# GFB_MCU_Testboard.net
KiCad netlist of a schematic drawn in EAGLE
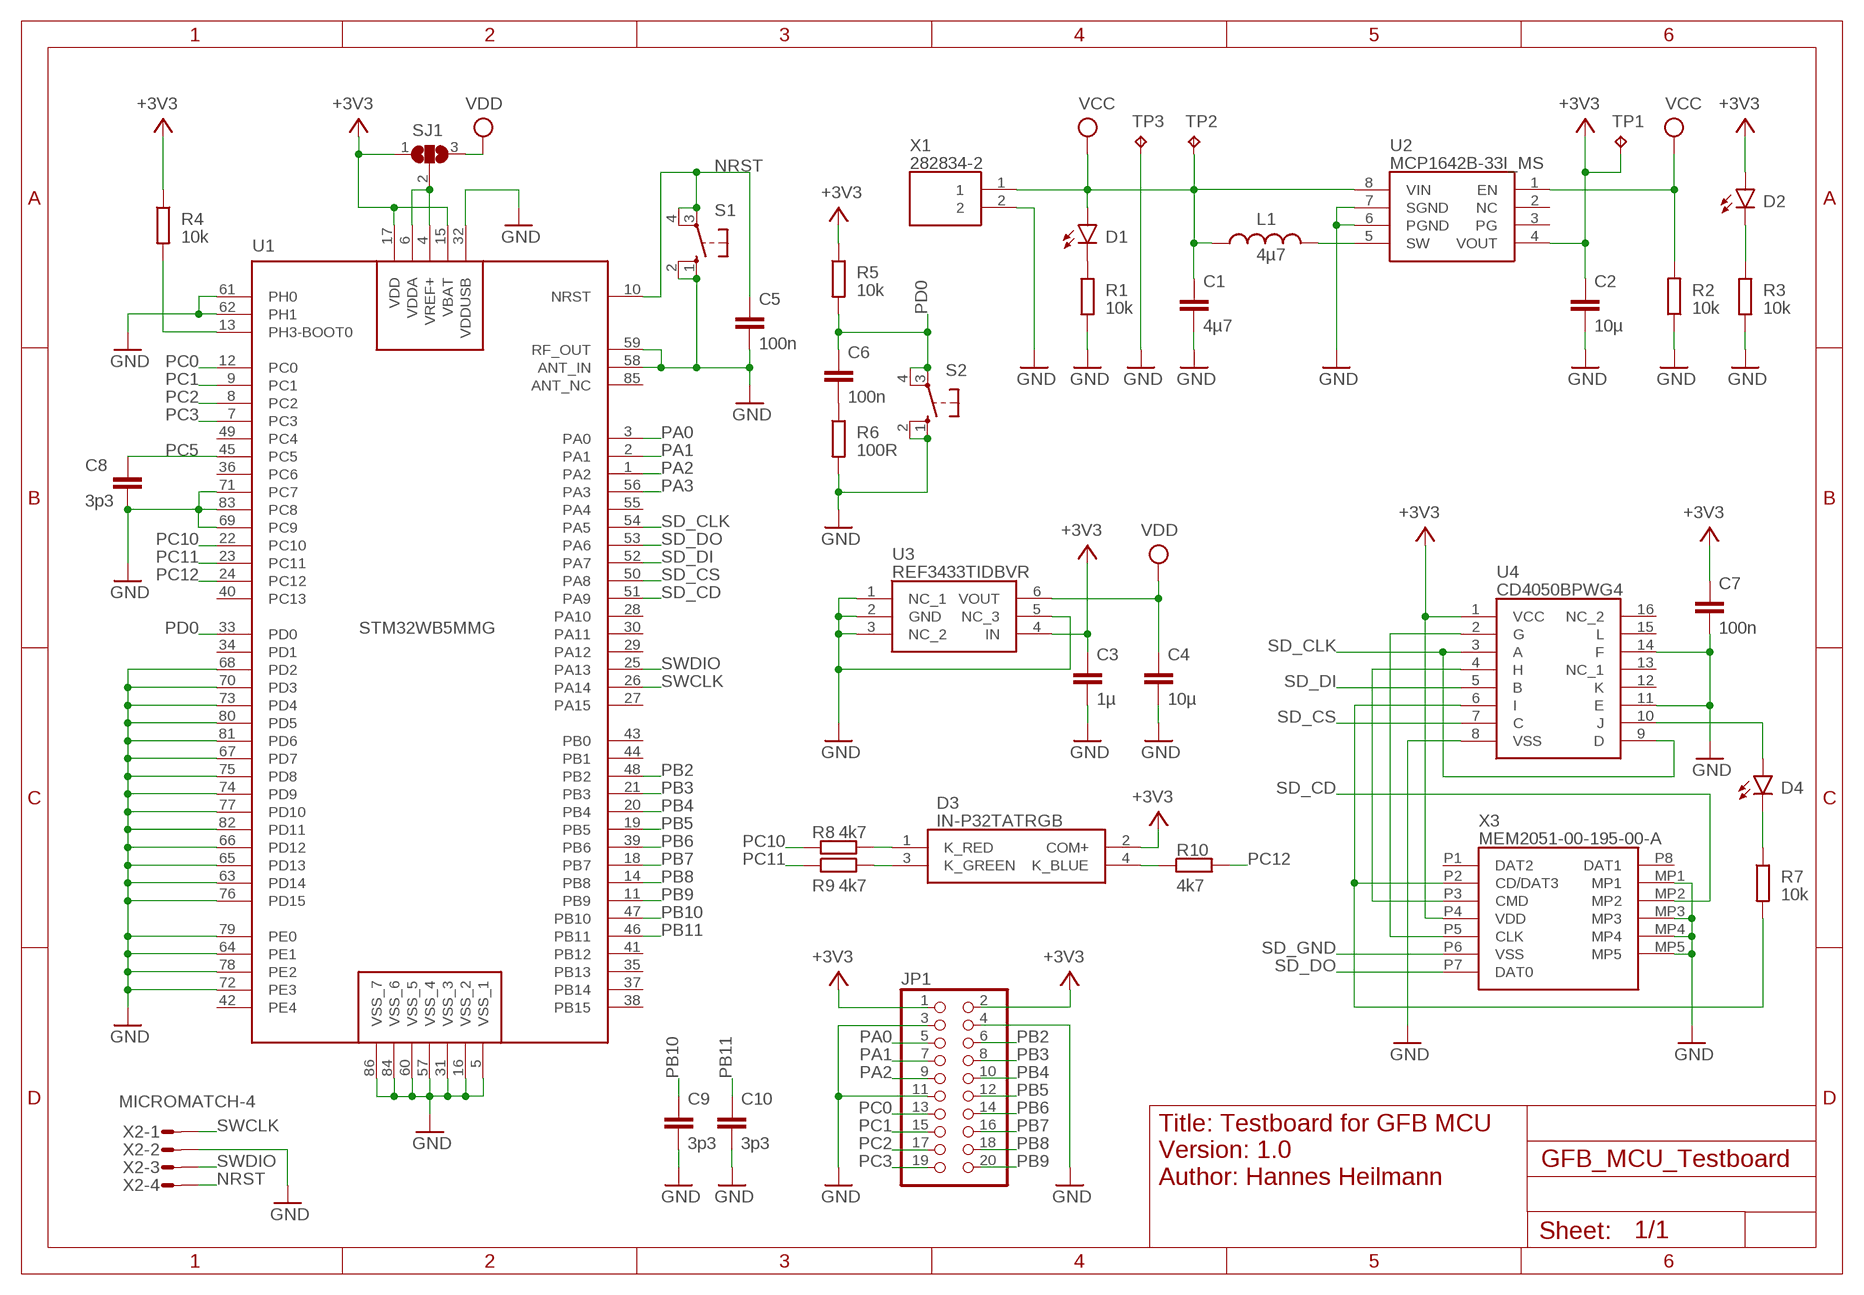
[diagram p0: schematic, sheet 1]

(export (version "E")
  (design (tool "Eeschema 10.0.6"))
  (components
    (comp (ref "C1")
      (value "4µ7")
      (footprint "eagle-import:C1206K")
      (libsource (lib "eagle-import") (part "C-EUC1206K"))
    )
    (comp (ref "C2")
      (value "10µ")
      (footprint "eagle-import:C1206K")
      (libsource (lib "eagle-import") (part "C-EUC1206K"))
    )
    (comp (ref "C3")
      (value "1µ")
      (footprint "eagle-import:C1206K")
      (libsource (lib "eagle-import") (part "C-EUC1206K"))
    )
    (comp (ref "C4")
      (value "10µ")
      (footprint "eagle-import:C1206K")
      (libsource (lib "eagle-import") (part "C-EUC1206K"))
    )
    (comp (ref "C5")
      (value "100n")
      (footprint "eagle-import:C0805K")
      (libsource (lib "eagle-import") (part "C-EUC0805K"))
    )
    (comp (ref "C6")
      (value "100n")
      (footprint "eagle-import:C0805K")
      (libsource (lib "eagle-import") (part "C-EUC0805K"))
    )
    (comp (ref "C7")
      (value "100n")
      (footprint "eagle-import:C0805K")
      (libsource (lib "eagle-import") (part "C-EUC0805K"))
    )
    (comp (ref "C8")
      (value "3p3")
      (footprint "eagle-import:C0805K")
      (libsource (lib "eagle-import") (part "C-EUC0805K"))
    )
    (comp (ref "C9")
      (value "3p3")
      (footprint "eagle-import:C0805K")
      (libsource (lib "eagle-import") (part "C-EUC0805K"))
    )
    (comp (ref "C10")
      (value "3p3")
      (footprint "eagle-import:C0805K")
      (libsource (lib "eagle-import") (part "C-EUC0805K"))
    )
    (comp (ref "D1")
      (value "LEDSML0805")
      (footprint "eagle-import:SML0805")
      (libsource (lib "eagle-import") (part "LEDSML0805"))
    )
    (comp (ref "D2")
      (value "LEDSML0805")
      (footprint "eagle-import:SML0805")
      (libsource (lib "eagle-import") (part "LEDSML0805"))
    )
    (comp (ref "D3")
      (value "IN-P32TATRGB")
      (footprint "eagle-import:INP32TATRGB")
      (fields (field (name "MOUSER_PART_NUMBER") "743-IN-P32TATRGB"))
      (libsource (lib "eagle-import") (part "IN-P32TATRGB"))
    )
    (comp (ref "D4")
      (value "LEDSML0805")
      (footprint "eagle-import:SML0805")
      (libsource (lib "eagle-import") (part "LEDSML0805"))
    )
    (comp (ref "JP1")
      (value "PINHD-2X10")
      (footprint "eagle-import:2X10")
      (libsource (lib "eagle-import") (part "PINHD-2X10"))
    )
    (comp (ref "L1")
      (value "4µ7")
      (footprint "eagle-import:L4532P")
      (libsource (lib "eagle-import") (part "L-USL4532P"))
    )
    (comp (ref "R1")
      (value "10k")
      (footprint "eagle-import:R0805")
      (libsource (lib "eagle-import") (part "R-EU_R0805"))
    )
    (comp (ref "R2")
      (value "10k")
      (footprint "eagle-import:R0805")
      (libsource (lib "eagle-import") (part "R-EU_R0805"))
    )
    (comp (ref "R3")
      (value "10k")
      (footprint "eagle-import:R0805")
      (libsource (lib "eagle-import") (part "R-EU_R0805"))
    )
    (comp (ref "R4")
      (value "10k")
      (footprint "eagle-import:R0805")
      (libsource (lib "eagle-import") (part "R-EU_R0805"))
    )
    (comp (ref "R5")
      (value "10k")
      (footprint "eagle-import:R0805")
      (libsource (lib "eagle-import") (part "R-EU_R0805"))
    )
    (comp (ref "R6")
      (value "100R")
      (footprint "eagle-import:R0805")
      (libsource (lib "eagle-import") (part "R-EU_R0805"))
    )
    (comp (ref "R7")
      (value "10k")
      (footprint "eagle-import:R0805")
      (libsource (lib "eagle-import") (part "R-EU_R0805"))
    )
    (comp (ref "R8")
      (value "4k7")
      (footprint "eagle-import:R0805")
      (libsource (lib "eagle-import") (part "R-EU_R0805"))
    )
    (comp (ref "R9")
      (value "4k7")
      (footprint "eagle-import:R0805")
      (libsource (lib "eagle-import") (part "R-EU_R0805"))
    )
    (comp (ref "R10")
      (value "4k7")
      (footprint "eagle-import:R0805")
      (libsource (lib "eagle-import") (part "R-EU_R0805"))
    )
    (comp (ref "S1")
      (value "10-XX")
      (footprint "eagle-import:B3F-10XX")
      (fields (field (name "MPN") "B3F-1000"))
      (libsource (lib "eagle-import") (part "10-XX"))
    )
    (comp (ref "S2")
      (value "10-XX")
      (footprint "eagle-import:B3F-10XX")
      (fields (field (name "MPN") "B3F-1000"))
      (libsource (lib "eagle-import") (part "10-XX"))
    )
    (comp (ref "SJ1")
      (value "SJ2W")
      (footprint "eagle-import:SJ_2")
      (libsource (lib "eagle-import") (part "SJ2W"))
    )
    (comp (ref "TP1")
      (value "TPB2,54")
      (footprint "eagle-import:B2,54")
      (libsource (lib "eagle-import") (part "TPB2,54"))
    )
    (comp (ref "TP2")
      (value "TPB2,54")
      (footprint "eagle-import:B2,54")
      (libsource (lib "eagle-import") (part "TPB2,54"))
    )
    (comp (ref "TP3")
      (value "TPB2,54")
      (footprint "eagle-import:B2,54")
      (libsource (lib "eagle-import") (part "TPB2,54"))
    )
    (comp (ref "U1")
      (value "STM32WB5MMG")
      (footprint "eagle-import:STM32WB5MMG")
      (libsource (lib "eagle-import") (part "STM32WB5MMG"))
    )
    (comp (ref "U2")
      (value "MCP1642B-33I_MS")
      (footprint "eagle-import:SOP65P490X110-8N")
      (fields
        (field (name "ARROW_PART_NUMBER") "MCP1642B-33I/MS")
        (field (name "MOUSER_PART_NUMBER") "579-MCP1642B-33I/MS")
      )
      (libsource (lib "eagle-import") (part "MCP1642B-33I_MS"))
    )
    (comp (ref "U3")
      (value "REF3433TIDBVR")
      (footprint "eagle-import:SOT95P280X145-6N")
      (fields (field (name "MOUSER_PART_NUMBER") "595-REF3433TIDBVR"))
      (libsource (lib "eagle-import") (part "REF3433TIDBVR"))
    )
    (comp (ref "U4")
      (value "CD4050BPWG4")
      (footprint "eagle-import:SOP65P640X120-16N")
      (libsource (lib "eagle-import") (part "CD4050BPWG4"))
    )
    (comp (ref "X1")
      (value "282834-2")
      (footprint "eagle-import:282834-2_1")
      (fields (field (name "MOUSER_PART_NUMBER") "571-282834-2"))
      (libsource (lib "eagle-import") (part "282834-2"))
    )
    (comp (ref "X2")
      (value "MICROMATCH-4")
      (footprint "eagle-import:MICROMATCH-4")
      (fields (field (name "MPN") "7-215464-4"))
      (libsource (lib "eagle-import") (part "MICROMATCH-4"))
    )
    (comp (ref "X3")
      (value "MEM2051-00-195-00-A")
      (footprint "eagle-import:MEM20510019500A")
      (fields (field (name "MOUSER_PART_NUMBER") "640-MEM20510019500A"))
      (libsource (lib "eagle-import") (part "MEM2051-00-195-00-A"))
    )
  )
  (nets
    (net (code "1") (name "+3V3") (class "Default")
      (node (ref "C2") (pin "1") (pinfunction "1_1") (pintype "passive"))
      (node (ref "C3") (pin "1") (pinfunction "1_1") (pintype "passive"))
      (node (ref "C7") (pin "1") (pinfunction "1_1") (pintype "passive"))
      (node (ref "D2") (pin "A") (pinfunction "A_A") (pintype "passive"))
      (node (ref "D3") (pin "2") (pinfunction "COM+_2") (pintype "bidirectional"))
      (node (ref "JP1") (pin "1") (pinfunction "1_1") (pintype "passive"))
      (node (ref "JP1") (pin "2") (pinfunction "2_2") (pintype "passive"))
      (node (ref "R4") (pin "1") (pinfunction "1_1") (pintype "passive"))
      (node (ref "R5") (pin "1") (pinfunction "1_1") (pintype "passive"))
      (node (ref "SJ1") (pin "1") (pinfunction "1_1") (pintype "passive"))
      (node (ref "TP1") (pin "TP") (pinfunction "TP_TP") (pintype "input"))
      (node (ref "U1") (pin "15") (pinfunction "VBAT_15") (pintype "power_in"))
      (node (ref "U1") (pin "17") (pinfunction "VDD_17") (pintype "power_in"))
      (node (ref "U2") (pin "4") (pinfunction "VOUT_4") (pintype "bidirectional"))
      (node (ref "U3") (pin "4") (pinfunction "IN_4") (pintype "input"))
      (node (ref "U4") (pin "1") (pinfunction "VCC_1") (pintype "bidirectional"))
      (node (ref "X3") (pin "P4") (pinfunction "VDD_P4") (pintype "bidirectional"))
    )
    (net (code "2") (name "/NRST") (class "Default")
      (node (ref "C5") (pin "1") (pinfunction "1_1") (pintype "passive"))
      (node (ref "S1") (pin "3") (pinfunction "P_3") (pintype "passive"))
      (node (ref "S1") (pin "4") (pinfunction "P1_4") (pintype "passive"))
      (node (ref "U1") (pin "10") (pinfunction "NRST_10") (pintype "power_in"))
      (node (ref "X2") (pin "4") (pinfunction "S_4") (pintype "passive"))
    )
    (net (code "3") (name "/PA0") (class "Default")
      (node (ref "JP1") (pin "5") (pinfunction "5_5") (pintype "passive"))
      (node (ref "U1") (pin "3") (pinfunction "PA0_3") (pintype "bidirectional"))
    )
    (net (code "4") (name "/PA1") (class "Default")
      (node (ref "JP1") (pin "7") (pinfunction "7_7") (pintype "passive"))
      (node (ref "U1") (pin "2") (pinfunction "PA1_2") (pintype "bidirectional"))
    )
    (net (code "5") (name "/PA2") (class "Default")
      (node (ref "JP1") (pin "9") (pinfunction "9_9") (pintype "passive"))
      (node (ref "U1") (pin "1") (pinfunction "PA2_1") (pintype "bidirectional"))
    )
    (net (code "6") (name "/PA3") (class "Default")
      (node (ref "U1") (pin "56") (pinfunction "PA3_56") (pintype "bidirectional"))
    )
    (net (code "7") (name "/PB2") (class "Default")
      (node (ref "JP1") (pin "6") (pinfunction "6_6") (pintype "passive"))
      (node (ref "U1") (pin "48") (pinfunction "PB2_48") (pintype "bidirectional"))
    )
    (net (code "8") (name "/PB3") (class "Default")
      (node (ref "JP1") (pin "8") (pinfunction "8_8") (pintype "passive"))
      (node (ref "U1") (pin "21") (pinfunction "PB3_21") (pintype "bidirectional"))
    )
    (net (code "9") (name "/PB4") (class "Default")
      (node (ref "JP1") (pin "10") (pinfunction "10_10") (pintype "passive"))
      (node (ref "U1") (pin "20") (pinfunction "PB4_20") (pintype "bidirectional"))
    )
    (net (code "10") (name "/PB5") (class "Default")
      (node (ref "JP1") (pin "12") (pinfunction "12_12") (pintype "passive"))
      (node (ref "U1") (pin "19") (pinfunction "PB5_19") (pintype "bidirectional"))
    )
    (net (code "11") (name "/PB6") (class "Default")
      (node (ref "JP1") (pin "14") (pinfunction "14_14") (pintype "passive"))
      (node (ref "U1") (pin "39") (pinfunction "PB6_39") (pintype "bidirectional"))
    )
    (net (code "12") (name "/PB7") (class "Default")
      (node (ref "JP1") (pin "16") (pinfunction "16_16") (pintype "passive"))
      (node (ref "U1") (pin "18") (pinfunction "PB7_18") (pintype "bidirectional"))
    )
    (net (code "13") (name "/PB8") (class "Default")
      (node (ref "JP1") (pin "18") (pinfunction "18_18") (pintype "passive"))
      (node (ref "U1") (pin "14") (pinfunction "PB8_14") (pintype "bidirectional"))
    )
    (net (code "14") (name "/PB9") (class "Default")
      (node (ref "JP1") (pin "20") (pinfunction "20_20") (pintype "passive"))
      (node (ref "U1") (pin "11") (pinfunction "PB9_11") (pintype "bidirectional"))
    )
    (net (code "15") (name "/PB10") (class "Default")
      (node (ref "C9") (pin "1") (pinfunction "1_1") (pintype "passive"))
      (node (ref "U1") (pin "47") (pinfunction "PB10_47") (pintype "bidirectional"))
    )
    (net (code "16") (name "/PB11") (class "Default")
      (node (ref "C10") (pin "1") (pinfunction "1_1") (pintype "passive"))
      (node (ref "U1") (pin "46") (pinfunction "PB11_46") (pintype "bidirectional"))
    )
    (net (code "17") (name "/PC0") (class "Default")
      (node (ref "JP1") (pin "13") (pinfunction "13_13") (pintype "passive"))
      (node (ref "U1") (pin "12") (pinfunction "PC0_12") (pintype "bidirectional"))
    )
    (net (code "18") (name "/PC1") (class "Default")
      (node (ref "JP1") (pin "15") (pinfunction "15_15") (pintype "passive"))
      (node (ref "U1") (pin "9") (pinfunction "PC1_9") (pintype "bidirectional"))
    )
    (net (code "19") (name "/PC2") (class "Default")
      (node (ref "JP1") (pin "17") (pinfunction "17_17") (pintype "passive"))
      (node (ref "U1") (pin "8") (pinfunction "PC2_8") (pintype "bidirectional"))
    )
    (net (code "20") (name "/PC3") (class "Default")
      (node (ref "JP1") (pin "19") (pinfunction "19_19") (pintype "passive"))
      (node (ref "U1") (pin "7") (pinfunction "PC3_7") (pintype "bidirectional"))
    )
    (net (code "21") (name "/PC5") (class "Default")
      (node (ref "C8") (pin "1") (pinfunction "1_1") (pintype "passive"))
      (node (ref "U1") (pin "45") (pinfunction "PC5_45") (pintype "bidirectional"))
    )
    (net (code "22") (name "/PC10") (class "Default")
      (node (ref "R8") (pin "1") (pinfunction "1_1") (pintype "passive"))
      (node (ref "U1") (pin "22") (pinfunction "PC10_22") (pintype "bidirectional"))
    )
    (net (code "23") (name "/PC11") (class "Default")
      (node (ref "R9") (pin "1") (pinfunction "1_1") (pintype "passive"))
      (node (ref "U1") (pin "23") (pinfunction "PC11_23") (pintype "bidirectional"))
    )
    (net (code "24") (name "/PC12") (class "Default")
      (node (ref "R10") (pin "2") (pinfunction "2_2") (pintype "passive"))
      (node (ref "U1") (pin "24") (pinfunction "PC12_24") (pintype "bidirectional"))
    )
    (net (code "25") (name "/PD0") (class "Default")
      (node (ref "C6") (pin "1") (pinfunction "1_1") (pintype "passive"))
      (node (ref "R5") (pin "2") (pinfunction "2_2") (pintype "passive"))
      (node (ref "S2") (pin "3") (pinfunction "P_3") (pintype "passive"))
      (node (ref "S2") (pin "4") (pinfunction "P1_4") (pintype "passive"))
      (node (ref "U1") (pin "33") (pinfunction "PD0_33") (pintype "bidirectional"))
    )
    (net (code "26") (name "/SD_CD") (class "Default")
      (node (ref "U1") (pin "51") (pinfunction "PA9_51") (pintype "bidirectional"))
      (node (ref "X3") (pin "MP2") (pinfunction "MP2_MP2") (pintype "bidirectional"))
    )
    (net (code "27") (name "/SD_CLK") (class "Default")
      (node (ref "U1") (pin "54") (pinfunction "PA5_54") (pintype "bidirectional"))
      (node (ref "U4") (pin "3") (pinfunction "A_3") (pintype "bidirectional"))
      (node (ref "U4") (pin "9") (pinfunction "D_9") (pintype "bidirectional"))
    )
    (net (code "28") (name "/SD_CS") (class "Default")
      (node (ref "U1") (pin "50") (pinfunction "PA8_50") (pintype "bidirectional"))
      (node (ref "U4") (pin "7") (pinfunction "C_7") (pintype "bidirectional"))
    )
    (net (code "29") (name "/SD_DI") (class "Default")
      (node (ref "U1") (pin "52") (pinfunction "PA7_52") (pintype "bidirectional"))
      (node (ref "U4") (pin "5") (pinfunction "B_5") (pintype "bidirectional"))
    )
    (net (code "30") (name "/SD_DO") (class "Default")
      (node (ref "U1") (pin "53") (pinfunction "PA6_53") (pintype "bidirectional"))
      (node (ref "X3") (pin "P7") (pinfunction "DAT0_P7") (pintype "bidirectional"))
    )
    (net (code "31") (name "/SD_GND") (class "Default")
      (node (ref "X3") (pin "P6") (pinfunction "VSS_P6") (pintype "bidirectional"))
    )
    (net (code "32") (name "/SWCLK") (class "Default")
      (node (ref "U1") (pin "26") (pinfunction "PA14_26") (pintype "bidirectional"))
      (node (ref "X2") (pin "1") (pinfunction "S_1") (pintype "passive"))
    )
    (net (code "33") (name "/SWDIO") (class "Default")
      (node (ref "U1") (pin "25") (pinfunction "PA13_25") (pintype "bidirectional"))
      (node (ref "X2") (pin "3") (pinfunction "S_3") (pintype "passive"))
    )
    (net (code "34") (name "GND") (class "Default")
      (node (ref "C1") (pin "2") (pinfunction "2_2") (pintype "passive"))
      (node (ref "C10") (pin "2") (pinfunction "2_2") (pintype "passive"))
      (node (ref "C2") (pin "2") (pinfunction "2_2") (pintype "passive"))
      (node (ref "C3") (pin "2") (pinfunction "2_2") (pintype "passive"))
      (node (ref "C4") (pin "2") (pinfunction "2_2") (pintype "passive"))
      (node (ref "C5") (pin "2") (pinfunction "2_2") (pintype "passive"))
      (node (ref "C7") (pin "2") (pinfunction "2_2") (pintype "passive"))
      (node (ref "C8") (pin "2") (pinfunction "2_2") (pintype "passive"))
      (node (ref "C9") (pin "2") (pinfunction "2_2") (pintype "passive"))
      (node (ref "JP1") (pin "11") (pinfunction "11_11") (pintype "passive"))
      (node (ref "JP1") (pin "3") (pinfunction "3_3") (pintype "passive"))
      (node (ref "JP1") (pin "4") (pinfunction "4_4") (pintype "passive"))
      (node (ref "R1") (pin "2") (pinfunction "2_2") (pintype "passive"))
      (node (ref "R2") (pin "1") (pinfunction "1_1") (pintype "passive"))
      (node (ref "R3") (pin "2") (pinfunction "2_2") (pintype "passive"))
      (node (ref "R6") (pin "2") (pinfunction "2_2") (pintype "passive"))
      (node (ref "S1") (pin "1") (pinfunction "S_1") (pintype "passive"))
      (node (ref "S1") (pin "2") (pinfunction "S1_2") (pintype "passive"))
      (node (ref "S2") (pin "1") (pinfunction "S_1") (pintype "passive"))
      (node (ref "S2") (pin "2") (pinfunction "S1_2") (pintype "passive"))
      (node (ref "TP3") (pin "TP") (pinfunction "TP_TP") (pintype "input"))
      (node (ref "U1") (pin "16") (pinfunction "VSS_2_16") (pintype "power_in"))
      (node (ref "U1") (pin "31") (pinfunction "VSS_3_31") (pintype "power_in"))
      (node (ref "U1") (pin "32") (pinfunction "VDDUSB_32") (pintype "power_in"))
      (node (ref "U1") (pin "5") (pinfunction "VSS_1_5") (pintype "power_in"))
      (node (ref "U1") (pin "57") (pinfunction "VSS_4_57") (pintype "power_in"))
      (node (ref "U1") (pin "58") (pinfunction "ANT_IN_58") (pintype "input"))
      (node (ref "U1") (pin "59") (pinfunction "RF_OUT_59") (pintype "output"))
      (node (ref "U1") (pin "60") (pinfunction "VSS_5_60") (pintype "power_in"))
      (node (ref "U1") (pin "61") (pinfunction "PH0_61") (pintype "power_in"))
      (node (ref "U1") (pin "62") (pinfunction "PH1_62") (pintype "power_in"))
      (node (ref "U1") (pin "63") (pinfunction "PD14_63") (pintype "bidirectional"))
      (node (ref "U1") (pin "64") (pinfunction "PE1_64") (pintype "bidirectional"))
      (node (ref "U1") (pin "65") (pinfunction "PD13_65") (pintype "bidirectional"))
      (node (ref "U1") (pin "66") (pinfunction "PD12_66") (pintype "bidirectional"))
      (node (ref "U1") (pin "67") (pinfunction "PD7_67") (pintype "bidirectional"))
      (node (ref "U1") (pin "68") (pinfunction "PD2_68") (pintype "bidirectional"))
      (node (ref "U1") (pin "69") (pinfunction "PC9_69") (pintype "bidirectional"))
      (node (ref "U1") (pin "70") (pinfunction "PD3_70") (pintype "bidirectional"))
      (node (ref "U1") (pin "71") (pinfunction "PC7_71") (pintype "bidirectional"))
      (node (ref "U1") (pin "72") (pinfunction "PE3_72") (pintype "bidirectional"))
      (node (ref "U1") (pin "73") (pinfunction "PD4_73") (pintype "bidirectional"))
      (node (ref "U1") (pin "74") (pinfunction "PD9_74") (pintype "bidirectional"))
      (node (ref "U1") (pin "75") (pinfunction "PD8_75") (pintype "bidirectional"))
      (node (ref "U1") (pin "76") (pinfunction "PD15_76") (pintype "bidirectional"))
      (node (ref "U1") (pin "77") (pinfunction "PD10_77") (pintype "bidirectional"))
      (node (ref "U1") (pin "78") (pinfunction "PE2_78") (pintype "bidirectional"))
      (node (ref "U1") (pin "79") (pinfunction "PE0_79") (pintype "bidirectional"))
      (node (ref "U1") (pin "80") (pinfunction "PD5_80") (pintype "bidirectional"))
      (node (ref "U1") (pin "81") (pinfunction "PD6_81") (pintype "bidirectional"))
      (node (ref "U1") (pin "82") (pinfunction "PD11_82") (pintype "bidirectional"))
      (node (ref "U1") (pin "83") (pinfunction "PC8_83") (pintype "bidirectional"))
      (node (ref "U1") (pin "84") (pinfunction "VSS_6_84") (pintype "power_in"))
      (node (ref "U1") (pin "86") (pinfunction "VSS_7_86") (pintype "power_in"))
      (node (ref "U2") (pin "6") (pinfunction "PGND_6") (pintype "bidirectional"))
      (node (ref "U2") (pin "7") (pinfunction "SGND_7") (pintype "bidirectional"))
      (node (ref "U3") (pin "1") (pinfunction "NC_1_1") (pintype "bidirectional"))
      (node (ref "U3") (pin "2") (pinfunction "GND_2") (pintype "power_in"))
      (node (ref "U3") (pin "3") (pinfunction "NC_2_3") (pintype "bidirectional"))
      (node (ref "U3") (pin "5") (pinfunction "NC_3_5") (pintype "bidirectional"))
      (node (ref "U4") (pin "11") (pinfunction "E_11") (pintype "bidirectional"))
      (node (ref "U4") (pin "14") (pinfunction "F_14") (pintype "bidirectional"))
      (node (ref "U4") (pin "8") (pinfunction "VSS_8") (pintype "bidirectional"))
      (node (ref "X1") (pin "2") (pinfunction "2_2") (pintype "bidirectional"))
      (node (ref "X2") (pin "2") (pinfunction "S_2") (pintype "passive"))
      (node (ref "X3") (pin "MP1") (pinfunction "MP1_MP1") (pintype "bidirectional"))
      (node (ref "X3") (pin "MP3") (pinfunction "MP3_MP3") (pintype "bidirectional"))
      (node (ref "X3") (pin "MP4") (pinfunction "MP4_MP4") (pintype "bidirectional"))
      (node (ref "X3") (pin "MP5") (pinfunction "MP5_MP5") (pintype "bidirectional"))
    )
    (net (code "35") (name "Net-(C6-Pad2)") (class "Default")
      (node (ref "C6") (pin "2") (pinfunction "2_2") (pintype "passive"))
      (node (ref "R6") (pin "1") (pinfunction "1_1") (pintype "passive"))
    )
    (net (code "36") (name "Net-(D1-PadC)") (class "Default")
      (node (ref "D1") (pin "C") (pinfunction "C_C") (pintype "passive"))
      (node (ref "R1") (pin "1") (pinfunction "1_1") (pintype "passive"))
    )
    (net (code "37") (name "Net-(D2-PadC)") (class "Default")
      (node (ref "D2") (pin "C") (pinfunction "C_C") (pintype "passive"))
      (node (ref "R3") (pin "1") (pinfunction "1_1") (pintype "passive"))
    )
    (net (code "38") (name "Net-(D3-K_BLUE)") (class "Default")
      (node (ref "D3") (pin "4") (pinfunction "K_BLUE_4") (pintype "bidirectional"))
      (node (ref "R10") (pin "1") (pinfunction "1_1") (pintype "passive"))
    )
    (net (code "39") (name "Net-(D3-K_GREEN)") (class "Default")
      (node (ref "D3") (pin "3") (pinfunction "K_GREEN_3") (pintype "bidirectional"))
      (node (ref "R9") (pin "2") (pinfunction "2_2") (pintype "passive"))
    )
    (net (code "40") (name "Net-(D3-K_RED)") (class "Default")
      (node (ref "D3") (pin "1") (pinfunction "K_RED_1") (pintype "bidirectional"))
      (node (ref "R8") (pin "2") (pinfunction "2_2") (pintype "passive"))
    )
    (net (code "41") (name "Net-(D4-PadC)") (class "Default")
      (node (ref "D4") (pin "C") (pinfunction "C_C") (pintype "passive"))
      (node (ref "R7") (pin "1") (pinfunction "1_1") (pintype "passive"))
    )
    (net (code "42") (name "Net-(U1-PH3-BOOT0)") (class "Default")
      (node (ref "R4") (pin "2") (pinfunction "2_2") (pintype "passive"))
      (node (ref "U1") (pin "13") (pinfunction "PH3-BOOT0_13") (pintype "power_in"))
    )
    (net (code "43") (name "Net-(U1-VDDA)") (class "Default")
      (node (ref "SJ1") (pin "2") (pinfunction "2_2") (pintype "passive"))
      (node (ref "U1") (pin "4") (pinfunction "VREF+_4") (pintype "power_in"))
      (node (ref "U1") (pin "6") (pinfunction "VDDA_6") (pintype "power_in"))
    )
    (net (code "44") (name "Net-(U2-SW)") (class "Default")
      (node (ref "L1") (pin "2") (pinfunction "2_2") (pintype "passive"))
      (node (ref "U2") (pin "5") (pinfunction "SW_5") (pintype "bidirectional"))
    )
    (net (code "45") (name "Net-(U4-G)") (class "Default")
      (node (ref "U4") (pin "2") (pinfunction "G_2") (pintype "bidirectional"))
      (node (ref "X3") (pin "P5") (pinfunction "CLK_P5") (pintype "bidirectional"))
    )
    (net (code "46") (name "Net-(U4-H)") (class "Default")
      (node (ref "U4") (pin "4") (pinfunction "H_4") (pintype "bidirectional"))
      (node (ref "X3") (pin "P3") (pinfunction "CMD_P3") (pintype "bidirectional"))
    )
    (net (code "47") (name "Net-(U4-I)") (class "Default")
      (node (ref "R7") (pin "2") (pinfunction "2_2") (pintype "passive"))
      (node (ref "U4") (pin "6") (pinfunction "I_6") (pintype "bidirectional"))
      (node (ref "X3") (pin "P2") (pinfunction "CD/DAT3_P2") (pintype "bidirectional"))
    )
    (net (code "48") (name "Net-(U4-J)") (class "Default")
      (node (ref "D4") (pin "A") (pinfunction "A_A") (pintype "passive"))
      (node (ref "U4") (pin "10") (pinfunction "J_10") (pintype "bidirectional"))
    )
    (net (code "49") (name "VCC") (class "Default")
      (node (ref "C1") (pin "1") (pinfunction "1_1") (pintype "passive"))
      (node (ref "D1") (pin "A") (pinfunction "A_A") (pintype "passive"))
      (node (ref "L1") (pin "1") (pinfunction "1_1") (pintype "passive"))
      (node (ref "R2") (pin "2") (pinfunction "2_2") (pintype "passive"))
      (node (ref "TP2") (pin "TP") (pinfunction "TP_TP") (pintype "input"))
      (node (ref "U2") (pin "1") (pinfunction "EN_1") (pintype "bidirectional"))
      (node (ref "U2") (pin "8") (pinfunction "VIN_8") (pintype "bidirectional"))
      (node (ref "X1") (pin "1") (pinfunction "1_1") (pintype "bidirectional"))
    )
    (net (code "50") (name "VDD") (class "Default")
      (node (ref "C4") (pin "1") (pinfunction "1_1") (pintype "passive"))
      (node (ref "SJ1") (pin "3") (pinfunction "3_3") (pintype "passive"))
      (node (ref "U3") (pin "6") (pinfunction "VOUT_6") (pintype "output"))
    )
    (net (code "51") (name "unconnected-(U1-ANT_NC-Pad85)") (class "Default")
      (node (ref "U1") (pin "85") (pinfunction "ANT_NC_85") (pintype "no_connect"))
    )
    (net (code "52") (name "unconnected-(U1-PA4-Pad55)") (class "Default")
      (node (ref "U1") (pin "55") (pinfunction "PA4_55") (pintype "bidirectional"))
    )
    (net (code "53") (name "unconnected-(U1-PA10-Pad28)") (class "Default")
      (node (ref "U1") (pin "28") (pinfunction "PA10_28") (pintype "bidirectional"))
    )
    (net (code "54") (name "unconnected-(U1-PA11-Pad30)") (class "Default")
      (node (ref "U1") (pin "30") (pinfunction "PA11_30") (pintype "bidirectional"))
    )
    (net (code "55") (name "unconnected-(U1-PA12-Pad29)") (class "Default")
      (node (ref "U1") (pin "29") (pinfunction "PA12_29") (pintype "bidirectional"))
    )
    (net (code "56") (name "unconnected-(U1-PA15-Pad27)") (class "Default")
      (node (ref "U1") (pin "27") (pinfunction "PA15_27") (pintype "bidirectional"))
    )
    (net (code "57") (name "unconnected-(U1-PB0-Pad43)") (class "Default")
      (node (ref "U1") (pin "43") (pinfunction "PB0_43") (pintype "no_connect"))
    )
    (net (code "58") (name "unconnected-(U1-PB1-Pad44)") (class "Default")
      (node (ref "U1") (pin "44") (pinfunction "PB1_44") (pintype "no_connect"))
    )
    (net (code "59") (name "unconnected-(U1-PB12-Pad41)") (class "Default")
      (node (ref "U1") (pin "41") (pinfunction "PB12_41") (pintype "bidirectional"))
    )
    (net (code "60") (name "unconnected-(U1-PB13-Pad35)") (class "Default")
      (node (ref "U1") (pin "35") (pinfunction "PB13_35") (pintype "bidirectional"))
    )
    (net (code "61") (name "unconnected-(U1-PB14-Pad37)") (class "Default")
      (node (ref "U1") (pin "37") (pinfunction "PB14_37") (pintype "bidirectional"))
    )
    (net (code "62") (name "unconnected-(U1-PB15-Pad38)") (class "Default")
      (node (ref "U1") (pin "38") (pinfunction "PB15_38") (pintype "bidirectional"))
    )
    (net (code "63") (name "unconnected-(U1-PC4-Pad49)") (class "Default")
      (node (ref "U1") (pin "49") (pinfunction "PC4_49") (pintype "bidirectional"))
    )
    (net (code "64") (name "unconnected-(U1-PC6-Pad36)") (class "Default")
      (node (ref "U1") (pin "36") (pinfunction "PC6_36") (pintype "bidirectional"))
    )
    (net (code "65") (name "unconnected-(U1-PC13-Pad40)") (class "Default")
      (node (ref "U1") (pin "40") (pinfunction "PC13_40") (pintype "bidirectional"))
    )
    (net (code "66") (name "unconnected-(U1-PD1-Pad34)") (class "Default")
      (node (ref "U1") (pin "34") (pinfunction "PD1_34") (pintype "bidirectional"))
    )
    (net (code "67") (name "unconnected-(U1-PE4-Pad42)") (class "Default")
      (node (ref "U1") (pin "42") (pinfunction "PE4_42") (pintype "bidirectional"))
    )
    (net (code "68") (name "unconnected-(U2-NC-Pad2)") (class "Default")
      (node (ref "U2") (pin "2") (pinfunction "NC_2") (pintype "no_connect"))
    )
    (net (code "69") (name "unconnected-(U2-PG-Pad3)") (class "Default")
      (node (ref "U2") (pin "3") (pinfunction "PG_3") (pintype "bidirectional"))
    )
    (net (code "70") (name "unconnected-(U4-K-Pad12)") (class "Default")
      (node (ref "U4") (pin "12") (pinfunction "K_12") (pintype "bidirectional"))
    )
    (net (code "71") (name "unconnected-(U4-L-Pad15)") (class "Default")
      (node (ref "U4") (pin "15") (pinfunction "L_15") (pintype "bidirectional"))
    )
    (net (code "72") (name "unconnected-(U4-NC_1-Pad13)") (class "Default")
      (node (ref "U4") (pin "13") (pinfunction "NC_1_13") (pintype "bidirectional"))
    )
    (net (code "73") (name "unconnected-(U4-NC_2-Pad16)") (class "Default")
      (node (ref "U4") (pin "16") (pinfunction "NC_2_16") (pintype "bidirectional"))
    )
    (net (code "74") (name "unconnected-(X3-DAT1-PadP8)") (class "Default")
      (node (ref "X3") (pin "P8") (pinfunction "DAT1_P8") (pintype "bidirectional"))
    )
    (net (code "75") (name "unconnected-(X3-DAT2-PadP1)") (class "Default")
      (node (ref "X3") (pin "P1") (pinfunction "DAT2_P1") (pintype "bidirectional"))
    )
  )
)
